# ESP826.net
KiCad netlist of a schematic drawn in Altium Designer
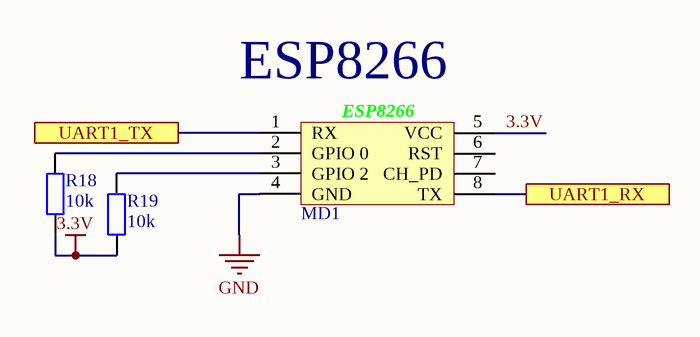
[diagram p0: ESP826.SchDoc]

(export (version "E")
  (design (tool "Eeschema 10.0.6"))
  (components
    (comp (ref "MD1")
      (value "ESP8266 Module")
      (footprint "ESP2866 Module")
      (libsource (lib "Altium_Lib_by_KhueNguyenCreator") (part "ESP8266 Module"))
    )
    (comp (ref "R18")
      (value "10k")
      (footprint "tro smd 0603")
      (description "Dán")
      (libsource (lib "Altium_Lib_by_KhueNguyenCreator") (part "Tro 0603 1% 10k"))
    )
    (comp (ref "R19")
      (value "10k")
      (footprint "tro smd 0603")
      (description "Dán")
      (libsource (lib "Altium_Lib_by_KhueNguyenCreator") (part "Tro 0603 1% 10k"))
    )
  )
  (nets
    (net (code "1") (name "/UART1_RX") (class "Default")
      (node (ref "MD1") (pin "8") (pinfunction "TX_8") (pintype "passive"))
    )
    (net (code "2") (name "/UART1_TX") (class "Default")
      (node (ref "MD1") (pin "1") (pinfunction "RX_1") (pintype "passive"))
    )
    (net (code "3") (name "3.3V") (class "Default")
      (node (ref "MD1") (pin "5") (pinfunction "VCC_5") (pintype "passive"))
      (node (ref "R18") (pin "1") (pinfunction "1_1") (pintype "passive"))
      (node (ref "R19") (pin "1") (pinfunction "1_1") (pintype "passive"))
    )
    (net (code "4") (name "GND") (class "Default")
      (node (ref "MD1") (pin "4") (pinfunction "GND_4") (pintype "passive"))
    )
    (net (code "5") (name "Net-(MD1-GPIO_0)") (class "Default")
      (node (ref "MD1") (pin "2") (pinfunction "GPIO_0_2") (pintype "passive"))
      (node (ref "R18") (pin "2") (pinfunction "2_2") (pintype "passive"))
    )
    (net (code "6") (name "Net-(MD1-GPIO_2)") (class "Default")
      (node (ref "MD1") (pin "3") (pinfunction "GPIO_2_3") (pintype "passive"))
      (node (ref "R19") (pin "2") (pinfunction "2_2") (pintype "passive"))
    )
    (net (code "7") (name "unconnected-(MD1-CH_PD-Pad7)") (class "Default")
      (node (ref "MD1") (pin "7") (pinfunction "CH_PD_7") (pintype "passive"))
    )
    (net (code "8") (name "unconnected-(MD1-RST-Pad6)") (class "Default")
      (node (ref "MD1") (pin "6") (pinfunction "RST_6") (pintype "passive"))
    )
  )
)
